# Fan_testing_rig_github.net
KiCad netlist of a schematic drawn in EasyEDA
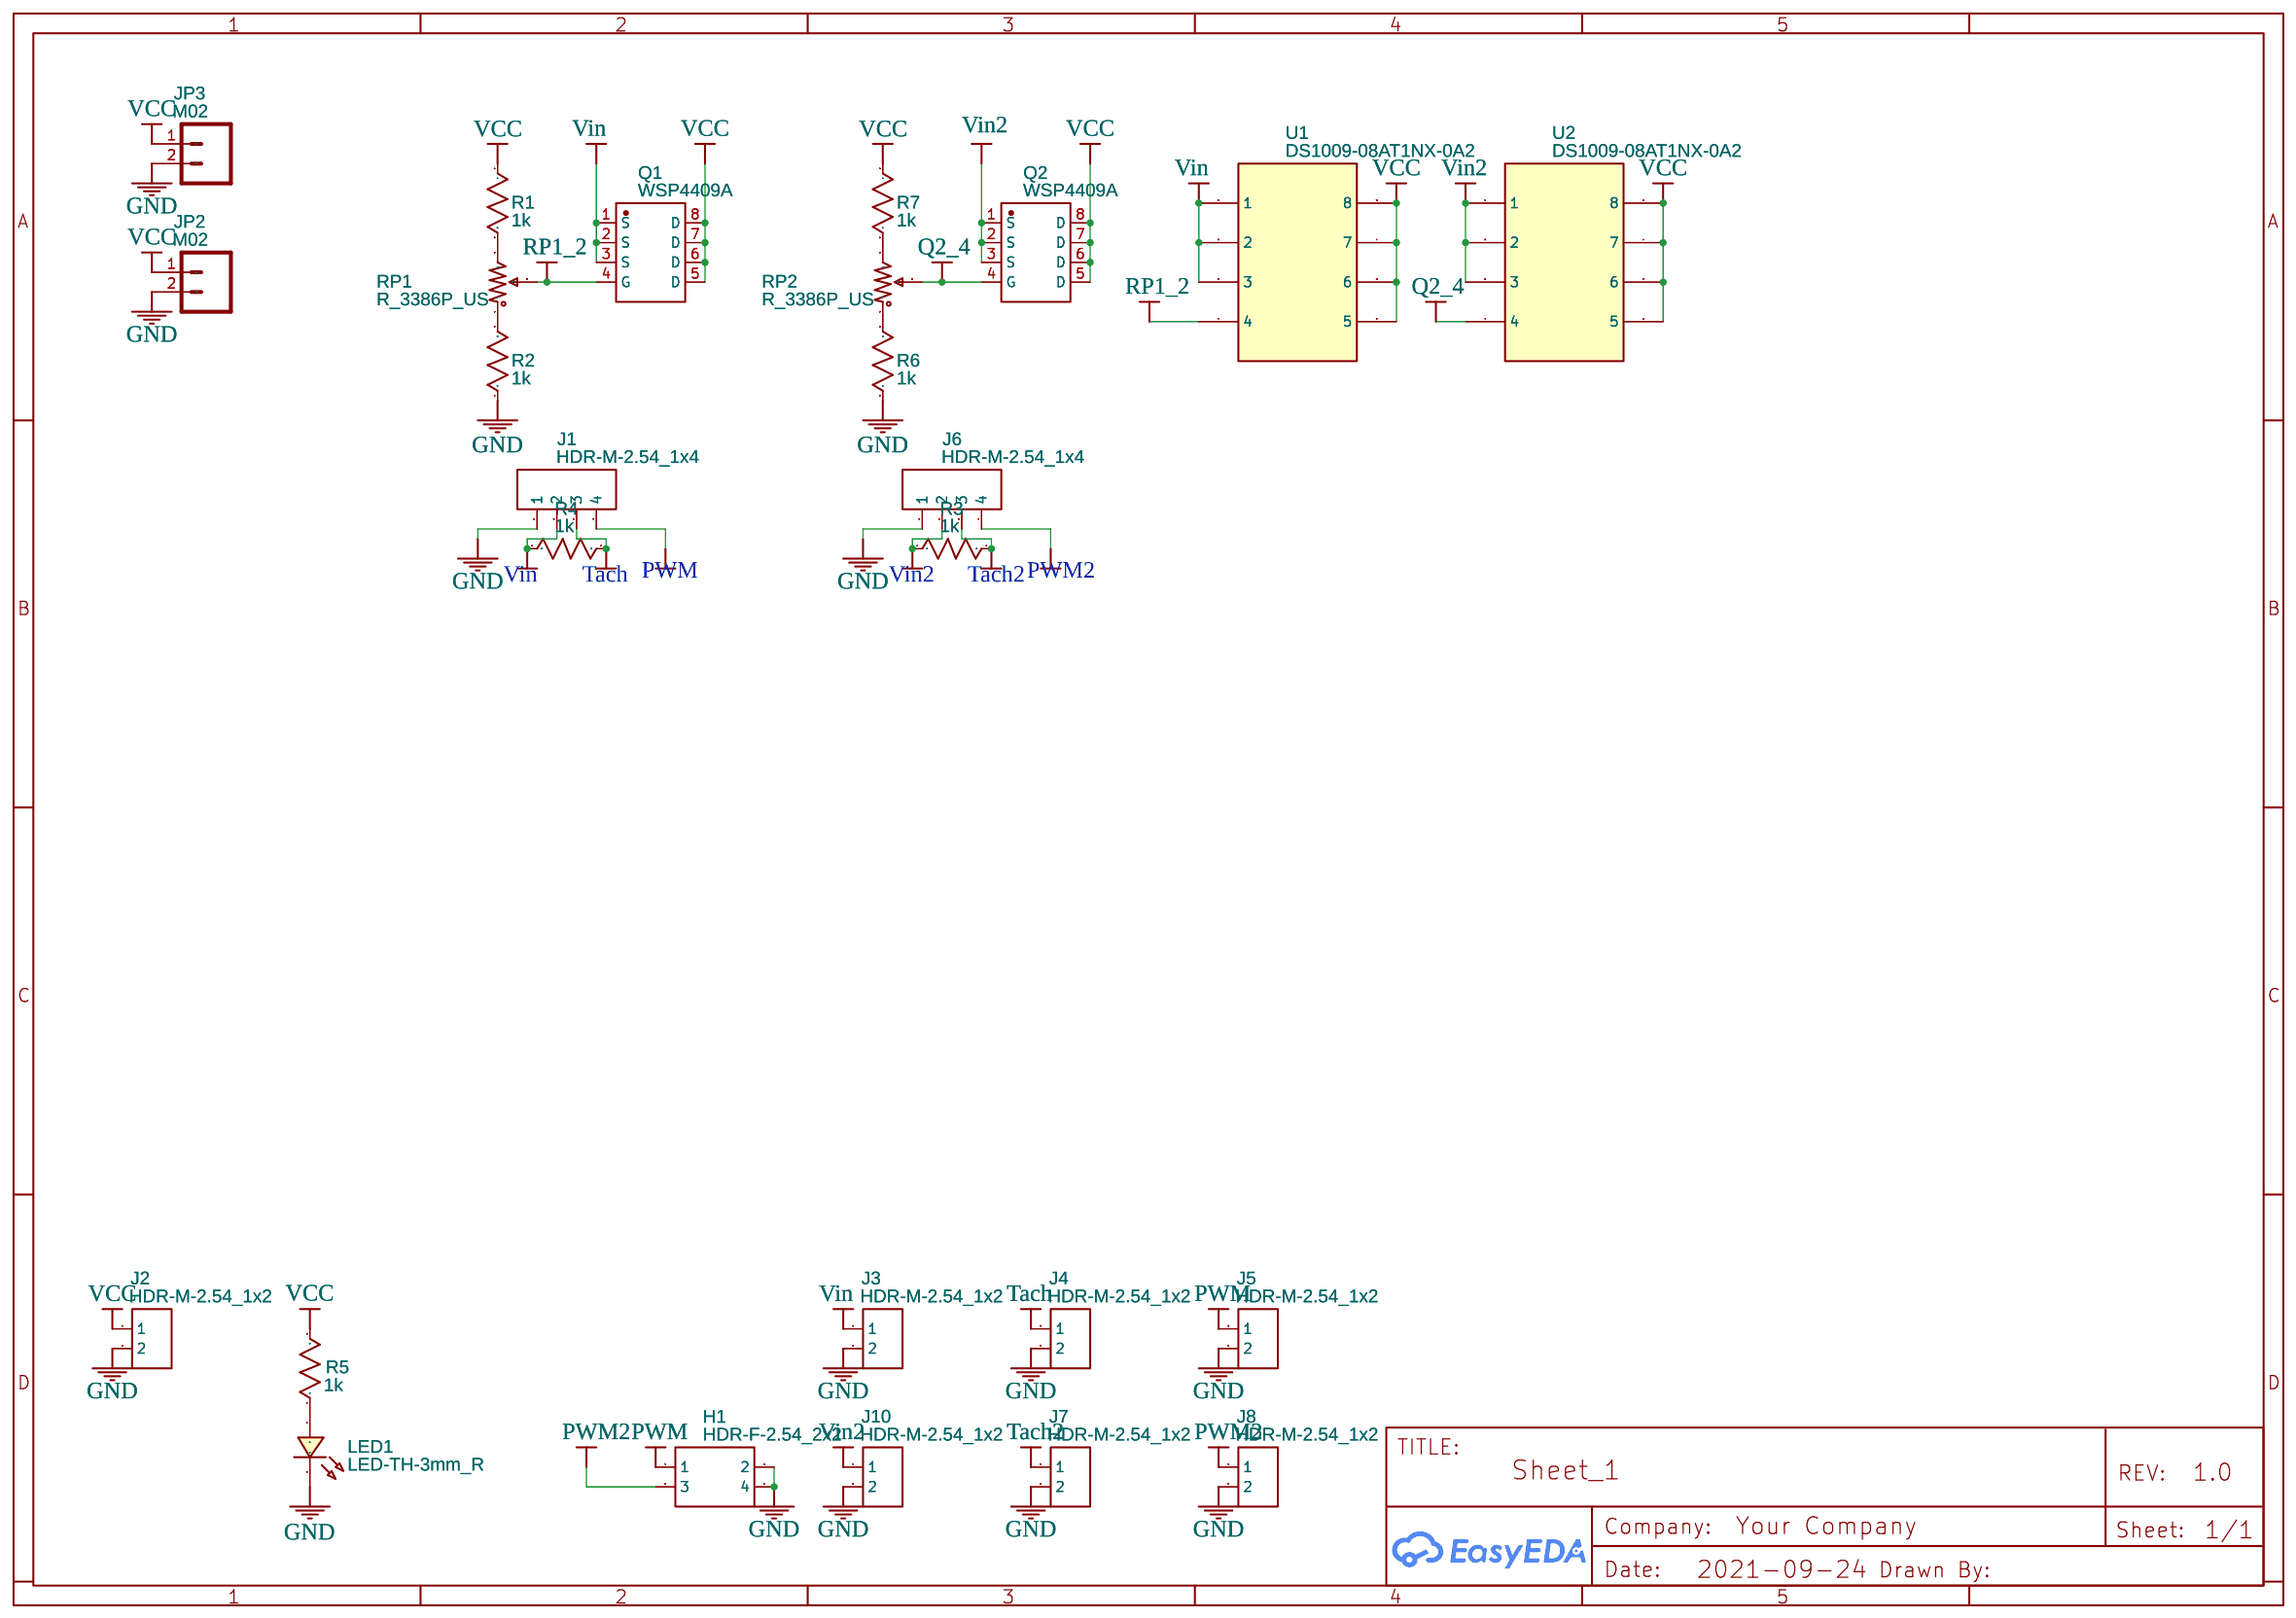
[diagram p0: main unit]
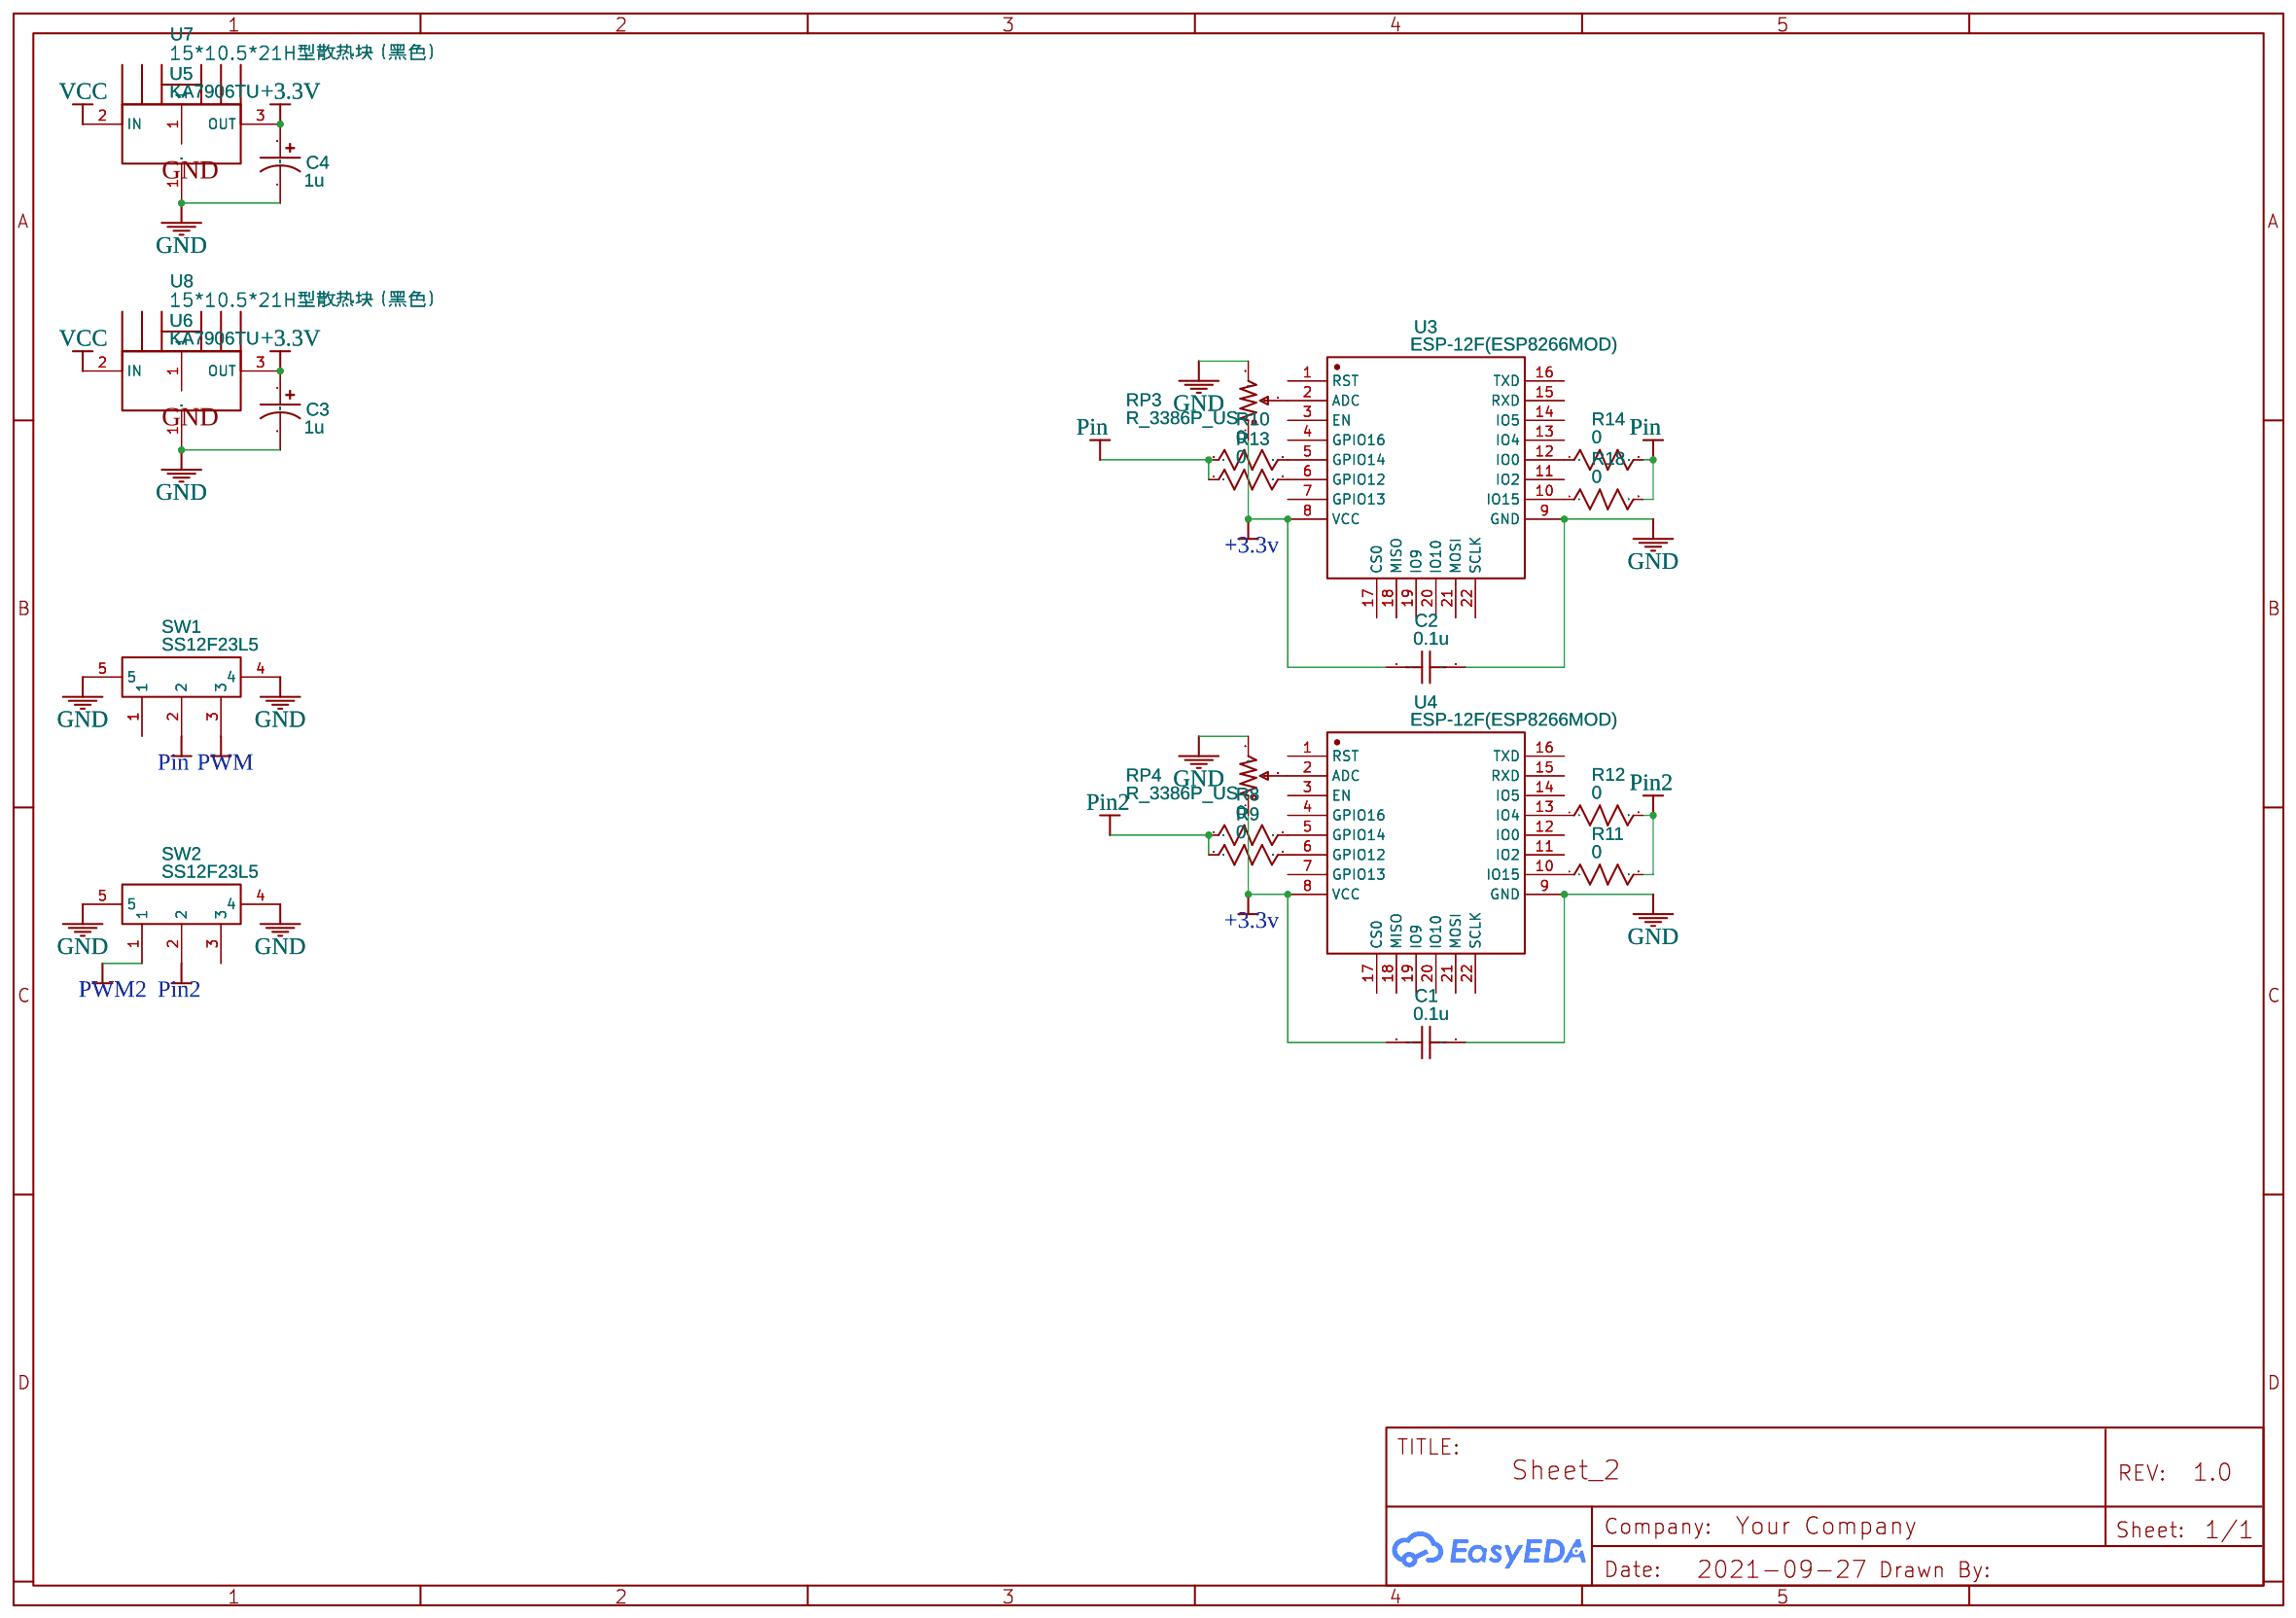
[diagram p1: PWM controll]

(export (version "E")
  (design (tool "Eeschema 10.0.6"))
  (components
    (comp (ref "H1")
      (value "HDR-F-2.54_2x2")
      (fields (field (name "BOM_Supplier Part") "C239342"))
      (libsource (lib "") (part "HDR-F-2.54_2x2"))
    )
    (comp (ref "J1")
      (value "HDR-M-2.54_1x4")
      (fields (field (name "BOM_Supplier Part") "C124378"))
      (libsource (lib "") (part "HDR-M-2.54_1x4"))
    )
    (comp (ref "J2")
      (value "HDR-M-2.54_1x2")
      (fields (field (name "BOM_Supplier Part") "C124375"))
      (libsource (lib "") (part "HDR-M-2.54_1x2"))
    )
    (comp (ref "J3")
      (value "HDR-M-2.54_1x2")
      (fields (field (name "BOM_Supplier Part") "C124375"))
      (libsource (lib "") (part "HDR-M-2.54_1x2"))
    )
    (comp (ref "J4")
      (value "HDR-M-2.54_1x2")
      (fields (field (name "BOM_Supplier Part") "C124375"))
      (libsource (lib "") (part "HDR-M-2.54_1x2"))
    )
    (comp (ref "J5")
      (value "HDR-M-2.54_1x2")
      (fields (field (name "BOM_Supplier Part") "C124375"))
      (libsource (lib "") (part "HDR-M-2.54_1x2"))
    )
    (comp (ref "J6")
      (value "HDR-M-2.54_1x4")
      (fields (field (name "BOM_Supplier Part") "C124378"))
      (libsource (lib "") (part "HDR-M-2.54_1x4"))
    )
    (comp (ref "J7")
      (value "HDR-M-2.54_1x2")
      (fields (field (name "BOM_Supplier Part") "C124375"))
      (libsource (lib "") (part "HDR-M-2.54_1x2"))
    )
    (comp (ref "J8")
      (value "HDR-M-2.54_1x2")
      (fields (field (name "BOM_Supplier Part") "C124375"))
      (libsource (lib "") (part "HDR-M-2.54_1x2"))
    )
    (comp (ref "J10")
      (value "HDR-M-2.54_1x2")
      (fields (field (name "BOM_Supplier Part") "C124375"))
      (libsource (lib "") (part "HDR-M-2.54_1x2"))
    )
    (comp (ref "JP2") (value "M02") (libsource (lib "") (part "M02")))
    (comp (ref "JP3") (value "M02") (libsource (lib "") (part "M02")))
    (comp (ref "LED1")
      (value "LED-TH-3mm_R")
      (fields
        (field (name "BOM_Manufacturer Part") "204-10SDRD/S530-A3-L")
        (field (name "BOM_Supplier Part") "C84774")
      )
      (libsource (lib "") (part "LED-TH-3mm_R"))
    )
    (comp (ref "Q1")
      (value "WSP4409A")
      (fields (field (name "BOM_Supplier Part") "C2880527"))
      (libsource (lib "") (part "WSP4409A"))
    )
    (comp (ref "Q2")
      (value "WSP4409A")
      (fields (field (name "BOM_Supplier Part") "C2880527"))
      (libsource (lib "") (part "WSP4409A"))
    )
    (comp (ref "R1") (value "1k") (libsource (lib "") (part "R_AXIAL-0.3_US_2")))
    (comp (ref "R2") (value "1k") (libsource (lib "") (part "R_AXIAL-0.3_US")))
    (comp (ref "R3") (value "1k") (libsource (lib "") (part "R_AXIAL-0.3_US_1")))
    (comp (ref "R4") (value "1k") (libsource (lib "") (part "R_AXIAL-0.3_US_1")))
    (comp (ref "R5") (value "1k") (libsource (lib "") (part "R_AXIAL-0.3_US")))
    (comp (ref "R6") (value "1k") (libsource (lib "") (part "R_AXIAL-0.3_US")))
    (comp (ref "R7") (value "1k") (libsource (lib "") (part "R_AXIAL-0.3_US_2")))
    (comp (ref "RP1") (value "R_3386P_US") (libsource (lib "") (part "R_3386P_US")))
    (comp (ref "RP2") (value "R_3386P_US") (libsource (lib "") (part "R_3386P_US")))
    (comp (ref "U1")
      (value "DS1009-08AT1NX-0A2")
      (fields (field (name "BOM_Supplier Part") "C72124"))
      (libsource (lib "") (part "DS1009-08AT1NX-0A2"))
    )
    (comp (ref "U2")
      (value "DS1009-08AT1NX-0A2")
      (fields (field (name "BOM_Supplier Part") "C72124"))
      (libsource (lib "") (part "DS1009-08AT1NX-0A2"))
    )
    (comp (ref "C1") (value "0.1u") (libsource (lib "") (part "C_0805_US")))
    (comp (ref "C2") (value "0.1u") (libsource (lib "") (part "C_0805_US")))
    (comp (ref "C3") (value "1u") (libsource (lib "") (part "CE_TH_D8.0×F3.5_US")))
    (comp (ref "C4") (value "1u") (libsource (lib "") (part "CE_TH_D8.0×F3.5_US")))
    (comp (ref "R8") (value "0") (libsource (lib "") (part "R_AXIAL-0.3_US")))
    (comp (ref "R9") (value "0") (libsource (lib "") (part "R_AXIAL-0.3_US")))
    (comp (ref "R10") (value "0") (libsource (lib "") (part "R_AXIAL-0.3_US")))
    (comp (ref "R11") (value "0") (libsource (lib "") (part "R_AXIAL-0.3_US")))
    (comp (ref "R12") (value "0") (libsource (lib "") (part "R_AXIAL-0.3_US")))
    (comp (ref "R13") (value "0") (libsource (lib "") (part "R_AXIAL-0.3_US")))
    (comp (ref "R14") (value "0") (libsource (lib "") (part "R_AXIAL-0.3_US")))
    (comp (ref "R18") (value "0") (libsource (lib "") (part "R_AXIAL-0.3_US")))
    (comp (ref "RP3") (value "R_3386P_US") (libsource (lib "") (part "R_3386P_US")))
    (comp (ref "RP4") (value "R_3386P_US") (libsource (lib "") (part "R_3386P_US")))
    (comp (ref "SW1")
      (value "SS12F23L5")
      (fields (field (name "BOM_Supplier Part") "C2884749"))
      (libsource (lib "") (part "SS12F23L5"))
    )
    (comp (ref "SW2")
      (value "SS12F23L5")
      (fields (field (name "BOM_Supplier Part") "C2884749"))
      (libsource (lib "") (part "SS12F23L5"))
    )
    (comp (ref "U3")
      (value "ESP-12F(ESP8266MOD)")
      (fields (field (name "BOM_Supplier Part") "C82891"))
      (libsource (lib "") (part "ESP-12F(ESP8266MOD)"))
    )
    (comp (ref "U4")
      (value "ESP-12F(ESP8266MOD)")
      (fields (field (name "BOM_Supplier Part") "C82891"))
      (libsource (lib "") (part "ESP-12F(ESP8266MOD)"))
    )
    (comp (ref "U5")
      (value "KA7906TU")
      (fields (field (name "BOM_Supplier Part") "C112610"))
      (libsource (lib "") (part "KA7906TU"))
    )
    (comp (ref "U6")
      (value "KA7906TU")
      (fields (field (name "BOM_Supplier Part") "C112610"))
      (libsource (lib "") (part "KA7906TU"))
    )
    (comp (ref "U7")
      (value "15*10.5*21H型散热块（黑色）")
      (fields (field (name "BOM_Supplier Part") "C116600"))
      (libsource (lib "") (part "15*10.5*21H型散热块（黑色）"))
    )
    (comp (ref "U8")
      (value "15*10.5*21H型散热块（黑色）")
      (fields (field (name "BOM_Supplier Part") "C116600"))
      (libsource (lib "") (part "15*10.5*21H型散热块（黑色）"))
    )
  )
  (nets
    (net (code "1") (name "+3.3V") (class "Default")
      (node (ref "C3") (pin "1") (pinfunction "1_1") (pintype "unspecified"))
      (node (ref "C4") (pin "1") (pinfunction "1_1") (pintype "unspecified"))
      (node (ref "U5") (pin "3") (pinfunction "OUT_3") (pintype "passive"))
      (node (ref "U6") (pin "3") (pinfunction "OUT_3") (pintype "passive"))
    )
    (net (code "2") (name "+3.3v") (class "Default")
      (node (ref "C1") (pin "1") (pinfunction "1_1") (pintype "unspecified"))
      (node (ref "C2") (pin "1") (pinfunction "1_1") (pintype "unspecified"))
      (node (ref "RP3") (pin "1") (pinfunction "1_1") (pintype "unspecified"))
      (node (ref "RP4") (pin "1") (pinfunction "1_1") (pintype "unspecified"))
      (node (ref "U3") (pin "8") (pinfunction "VCC_8") (pintype "unspecified"))
      (node (ref "U4") (pin "8") (pinfunction "VCC_8") (pintype "unspecified"))
    )
    (net (code "3") (name "GND") (class "Default")
      (node (ref "C1") (pin "2") (pinfunction "2_2") (pintype "unspecified"))
      (node (ref "C2") (pin "2") (pinfunction "2_2") (pintype "unspecified"))
      (node (ref "C3") (pin "2") (pinfunction "2_2") (pintype "unspecified"))
      (node (ref "C4") (pin "2") (pinfunction "2_2") (pintype "unspecified"))
      (node (ref "H1") (pin "2") (pinfunction "2_2") (pintype "unspecified"))
      (node (ref "H1") (pin "4") (pinfunction "4_4") (pintype "unspecified"))
      (node (ref "J1") (pin "1") (pinfunction "1_1") (pintype "unspecified"))
      (node (ref "J10") (pin "2") (pinfunction "2_2") (pintype "unspecified"))
      (node (ref "J2") (pin "2") (pinfunction "2_2") (pintype "unspecified"))
      (node (ref "J3") (pin "2") (pinfunction "2_2") (pintype "unspecified"))
      (node (ref "J4") (pin "2") (pinfunction "2_2") (pintype "unspecified"))
      (node (ref "J5") (pin "2") (pinfunction "2_2") (pintype "unspecified"))
      (node (ref "J6") (pin "1") (pinfunction "1_1") (pintype "unspecified"))
      (node (ref "J7") (pin "2") (pinfunction "2_2") (pintype "unspecified"))
      (node (ref "J8") (pin "2") (pinfunction "2_2") (pintype "unspecified"))
      (node (ref "JP2") (pin "2") (pinfunction "2_2") (pintype "unspecified"))
      (node (ref "JP3") (pin "2") (pinfunction "2_2") (pintype "unspecified"))
      (node (ref "LED1") (pin "2") (pinfunction "2_2") (pintype "unspecified"))
      (node (ref "R2") (pin "1") (pinfunction "1_1") (pintype "unspecified"))
      (node (ref "R6") (pin "1") (pinfunction "1_1") (pintype "unspecified"))
      (node (ref "RP3") (pin "3") (pinfunction "3_3") (pintype "unspecified"))
      (node (ref "RP4") (pin "3") (pinfunction "3_3") (pintype "unspecified"))
      (node (ref "SW1") (pin "4") (pinfunction "4_4") (pintype "unspecified"))
      (node (ref "SW1") (pin "5") (pinfunction "5_5") (pintype "unspecified"))
      (node (ref "SW2") (pin "4") (pinfunction "4_4") (pintype "unspecified"))
      (node (ref "SW2") (pin "5") (pinfunction "5_5") (pintype "unspecified"))
      (node (ref "U3") (pin "9") (pinfunction "GND_9") (pintype "unspecified"))
      (node (ref "U4") (pin "9") (pinfunction "GND_9") (pintype "unspecified"))
      (node (ref "U5") (pin "1") (pinfunction "GND_1") (pintype "passive"))
      (node (ref "U6") (pin "1") (pinfunction "GND_1") (pintype "passive"))
    )
    (net (code "4") (name "Net-(LED1-Pad1)") (class "Default")
      (node (ref "LED1") (pin "1") (pinfunction "1_1") (pintype "unspecified"))
      (node (ref "R5") (pin "1") (pinfunction "1_1") (pintype "unspecified"))
    )
    (net (code "5") (name "Net-(R1-Pad2)") (class "Default")
      (node (ref "R1") (pin "2") (pinfunction "2_2") (pintype "unspecified"))
      (node (ref "RP1") (pin "3") (pinfunction "3_3") (pintype "unspecified"))
    )
    (net (code "6") (name "Net-(R2-Pad2)") (class "Default")
      (node (ref "R2") (pin "2") (pinfunction "2_2") (pintype "unspecified"))
      (node (ref "RP1") (pin "1") (pinfunction "1_1") (pintype "unspecified"))
    )
    (net (code "7") (name "Net-(R6-Pad2)") (class "Default")
      (node (ref "R6") (pin "2") (pinfunction "2_2") (pintype "unspecified"))
      (node (ref "RP2") (pin "1") (pinfunction "1_1") (pintype "unspecified"))
    )
    (net (code "8") (name "Net-(R7-Pad2)") (class "Default")
      (node (ref "R7") (pin "2") (pinfunction "2_2") (pintype "unspecified"))
      (node (ref "RP2") (pin "3") (pinfunction "3_3") (pintype "unspecified"))
    )
    (net (code "9") (name "Net-(U3-ADC)") (class "Default")
      (node (ref "RP3") (pin "2") (pinfunction "2_2") (pintype "unspecified"))
      (node (ref "U3") (pin "2") (pinfunction "ADC_2") (pintype "unspecified"))
    )
    (net (code "10") (name "Net-(U3-GPIO12)") (class "Default")
      (node (ref "R13") (pin "2") (pinfunction "2_2") (pintype "unspecified"))
      (node (ref "U3") (pin "6") (pinfunction "GPIO12_6") (pintype "unspecified"))
    )
    (net (code "11") (name "Net-(U3-GPIO14)") (class "Default")
      (node (ref "R10") (pin "2") (pinfunction "2_2") (pintype "unspecified"))
      (node (ref "U3") (pin "5") (pinfunction "GPIO14_5") (pintype "unspecified"))
    )
    (net (code "12") (name "Net-(U3-IO0)") (class "Default")
      (node (ref "R14") (pin "1") (pinfunction "1_1") (pintype "unspecified"))
      (node (ref "U3") (pin "12") (pinfunction "IO0_12") (pintype "unspecified"))
    )
    (net (code "13") (name "Net-(U3-IO15)") (class "Default")
      (node (ref "R18") (pin "1") (pinfunction "1_1") (pintype "unspecified"))
      (node (ref "U3") (pin "10") (pinfunction "IO15_10") (pintype "unspecified"))
    )
    (net (code "14") (name "Net-(U4-ADC)") (class "Default")
      (node (ref "RP4") (pin "2") (pinfunction "2_2") (pintype "unspecified"))
      (node (ref "U4") (pin "2") (pinfunction "ADC_2") (pintype "unspecified"))
    )
    (net (code "15") (name "Net-(U4-GPIO12)") (class "Default")
      (node (ref "R9") (pin "2") (pinfunction "2_2") (pintype "unspecified"))
      (node (ref "U4") (pin "6") (pinfunction "GPIO12_6") (pintype "unspecified"))
    )
    (net (code "16") (name "Net-(U4-GPIO14)") (class "Default")
      (node (ref "R8") (pin "2") (pinfunction "2_2") (pintype "unspecified"))
      (node (ref "U4") (pin "5") (pinfunction "GPIO14_5") (pintype "unspecified"))
    )
    (net (code "17") (name "Net-(U4-IO4)") (class "Default")
      (node (ref "R12") (pin "1") (pinfunction "1_1") (pintype "unspecified"))
      (node (ref "U4") (pin "13") (pinfunction "IO4_13") (pintype "unspecified"))
    )
    (net (code "18") (name "Net-(U4-IO15)") (class "Default")
      (node (ref "R11") (pin "1") (pinfunction "1_1") (pintype "unspecified"))
      (node (ref "U4") (pin "10") (pinfunction "IO15_10") (pintype "unspecified"))
    )
    (net (code "19") (name "PWM") (class "Default")
      (node (ref "H1") (pin "1") (pinfunction "1_1") (pintype "unspecified"))
      (node (ref "J1") (pin "4") (pinfunction "4_4") (pintype "unspecified"))
      (node (ref "J5") (pin "1") (pinfunction "1_1") (pintype "unspecified"))
      (node (ref "SW1") (pin "3") (pinfunction "3_3") (pintype "unspecified"))
    )
    (net (code "20") (name "PWM2") (class "Default")
      (node (ref "H1") (pin "3") (pinfunction "3_3") (pintype "unspecified"))
      (node (ref "J6") (pin "4") (pinfunction "4_4") (pintype "unspecified"))
      (node (ref "J8") (pin "1") (pinfunction "1_1") (pintype "unspecified"))
      (node (ref "SW2") (pin "1") (pinfunction "1_1") (pintype "unspecified"))
    )
    (net (code "21") (name "Pin") (class "Default")
      (node (ref "R10") (pin "1") (pinfunction "1_1") (pintype "unspecified"))
      (node (ref "R13") (pin "1") (pinfunction "1_1") (pintype "unspecified"))
      (node (ref "R14") (pin "2") (pinfunction "2_2") (pintype "unspecified"))
      (node (ref "R18") (pin "2") (pinfunction "2_2") (pintype "unspecified"))
      (node (ref "SW1") (pin "2") (pinfunction "2_2") (pintype "unspecified"))
    )
    (net (code "22") (name "Pin2") (class "Default")
      (node (ref "R11") (pin "2") (pinfunction "2_2") (pintype "unspecified"))
      (node (ref "R12") (pin "2") (pinfunction "2_2") (pintype "unspecified"))
      (node (ref "R8") (pin "1") (pinfunction "1_1") (pintype "unspecified"))
      (node (ref "R9") (pin "1") (pinfunction "1_1") (pintype "unspecified"))
      (node (ref "SW2") (pin "2") (pinfunction "2_2") (pintype "unspecified"))
    )
    (net (code "23") (name "Q2_4") (class "Default")
      (node (ref "Q2") (pin "4") (pinfunction "G_4") (pintype "unspecified"))
      (node (ref "RP2") (pin "2") (pinfunction "2_2") (pintype "unspecified"))
      (node (ref "U2") (pin "4") (pinfunction "4_4") (pintype "input"))
    )
    (net (code "24") (name "RP1_2") (class "Default")
      (node (ref "Q1") (pin "4") (pinfunction "G_4") (pintype "unspecified"))
      (node (ref "RP1") (pin "2") (pinfunction "2_2") (pintype "unspecified"))
      (node (ref "U1") (pin "4") (pinfunction "4_4") (pintype "input"))
    )
    (net (code "25") (name "Tach") (class "Default")
      (node (ref "J1") (pin "3") (pinfunction "3_3") (pintype "unspecified"))
      (node (ref "J4") (pin "1") (pinfunction "1_1") (pintype "unspecified"))
      (node (ref "R4") (pin "2") (pinfunction "2_2") (pintype "unspecified"))
    )
    (net (code "26") (name "Tach2") (class "Default")
      (node (ref "J6") (pin "3") (pinfunction "3_3") (pintype "unspecified"))
      (node (ref "J7") (pin "1") (pinfunction "1_1") (pintype "unspecified"))
      (node (ref "R3") (pin "2") (pinfunction "2_2") (pintype "unspecified"))
    )
    (net (code "27") (name "VCC") (class "Default")
      (node (ref "J2") (pin "1") (pinfunction "1_1") (pintype "unspecified"))
      (node (ref "JP2") (pin "1") (pinfunction "1_1") (pintype "unspecified"))
      (node (ref "JP3") (pin "1") (pinfunction "1_1") (pintype "unspecified"))
      (node (ref "Q1") (pin "5") (pinfunction "D_5") (pintype "unspecified"))
      (node (ref "Q1") (pin "6") (pinfunction "D_6") (pintype "unspecified"))
      (node (ref "Q1") (pin "7") (pinfunction "D_7") (pintype "unspecified"))
      (node (ref "Q1") (pin "8") (pinfunction "D_8") (pintype "unspecified"))
      (node (ref "Q2") (pin "5") (pinfunction "D_5") (pintype "unspecified"))
      (node (ref "Q2") (pin "6") (pinfunction "D_6") (pintype "unspecified"))
      (node (ref "Q2") (pin "7") (pinfunction "D_7") (pintype "unspecified"))
      (node (ref "Q2") (pin "8") (pinfunction "D_8") (pintype "unspecified"))
      (node (ref "R1") (pin "1") (pinfunction "1_1") (pintype "unspecified"))
      (node (ref "R5") (pin "2") (pinfunction "2_2") (pintype "unspecified"))
      (node (ref "R7") (pin "1") (pinfunction "1_1") (pintype "unspecified"))
      (node (ref "U1") (pin "5") (pinfunction "5_5") (pintype "input"))
      (node (ref "U1") (pin "6") (pinfunction "6_6") (pintype "input"))
      (node (ref "U1") (pin "7") (pinfunction "7_7") (pintype "input"))
      (node (ref "U1") (pin "8") (pinfunction "8_8") (pintype "input"))
      (node (ref "U2") (pin "5") (pinfunction "5_5") (pintype "input"))
      (node (ref "U2") (pin "6") (pinfunction "6_6") (pintype "input"))
      (node (ref "U2") (pin "7") (pinfunction "7_7") (pintype "input"))
      (node (ref "U2") (pin "8") (pinfunction "8_8") (pintype "input"))
      (node (ref "U5") (pin "2") (pinfunction "IN_2") (pintype "passive"))
      (node (ref "U6") (pin "2") (pinfunction "IN_2") (pintype "passive"))
    )
    (net (code "28") (name "Vin") (class "Default")
      (node (ref "J1") (pin "2") (pinfunction "2_2") (pintype "unspecified"))
      (node (ref "J3") (pin "1") (pinfunction "1_1") (pintype "unspecified"))
      (node (ref "Q1") (pin "1") (pinfunction "S_1") (pintype "unspecified"))
      (node (ref "Q1") (pin "2") (pinfunction "S_2") (pintype "unspecified"))
      (node (ref "Q1") (pin "3") (pinfunction "S_3") (pintype "unspecified"))
      (node (ref "R4") (pin "1") (pinfunction "1_1") (pintype "unspecified"))
      (node (ref "U1") (pin "1") (pinfunction "1_1") (pintype "input"))
      (node (ref "U1") (pin "2") (pinfunction "2_2") (pintype "input"))
      (node (ref "U1") (pin "3") (pinfunction "3_3") (pintype "input"))
    )
    (net (code "29") (name "Vin2") (class "Default")
      (node (ref "J10") (pin "1") (pinfunction "1_1") (pintype "unspecified"))
      (node (ref "J6") (pin "2") (pinfunction "2_2") (pintype "unspecified"))
      (node (ref "Q2") (pin "1") (pinfunction "S_1") (pintype "unspecified"))
      (node (ref "Q2") (pin "2") (pinfunction "S_2") (pintype "unspecified"))
      (node (ref "Q2") (pin "3") (pinfunction "S_3") (pintype "unspecified"))
      (node (ref "R3") (pin "1") (pinfunction "1_1") (pintype "unspecified"))
      (node (ref "U2") (pin "1") (pinfunction "1_1") (pintype "input"))
      (node (ref "U2") (pin "2") (pinfunction "2_2") (pintype "input"))
      (node (ref "U2") (pin "3") (pinfunction "3_3") (pintype "input"))
    )
    (net (code "30") (name "unconnected-(SW1-Pad1)") (class "Default")
      (node (ref "SW1") (pin "1") (pinfunction "1_1") (pintype "unspecified"))
    )
    (net (code "31") (name "unconnected-(SW2-Pad3)") (class "Default")
      (node (ref "SW2") (pin "3") (pinfunction "3_3") (pintype "unspecified"))
    )
    (net (code "32") (name "unconnected-(U3-CS0-Pad17)") (class "Default")
      (node (ref "U3") (pin "17") (pinfunction "CS0_17") (pintype "unspecified"))
    )
    (net (code "33") (name "unconnected-(U3-EN-Pad3)") (class "Default")
      (node (ref "U3") (pin "3") (pinfunction "EN_3") (pintype "unspecified"))
    )
    (net (code "34") (name "unconnected-(U3-GPIO13-Pad7)") (class "Default")
      (node (ref "U3") (pin "7") (pinfunction "GPIO13_7") (pintype "unspecified"))
    )
    (net (code "35") (name "unconnected-(U3-GPIO16-Pad4)") (class "Default")
      (node (ref "U3") (pin "4") (pinfunction "GPIO16_4") (pintype "unspecified"))
    )
    (net (code "36") (name "unconnected-(U3-IO2-Pad11)") (class "Default")
      (node (ref "U3") (pin "11") (pinfunction "IO2_11") (pintype "unspecified"))
    )
    (net (code "37") (name "unconnected-(U3-IO4-Pad13)") (class "Default")
      (node (ref "U3") (pin "13") (pinfunction "IO4_13") (pintype "unspecified"))
    )
    (net (code "38") (name "unconnected-(U3-IO5-Pad14)") (class "Default")
      (node (ref "U3") (pin "14") (pinfunction "IO5_14") (pintype "unspecified"))
    )
    (net (code "39") (name "unconnected-(U3-IO9-Pad19)") (class "Default")
      (node (ref "U3") (pin "19") (pinfunction "IO9_19") (pintype "unspecified"))
    )
    (net (code "40") (name "unconnected-(U3-IO10-Pad20)") (class "Default")
      (node (ref "U3") (pin "20") (pinfunction "IO10_20") (pintype "unspecified"))
    )
    (net (code "41") (name "unconnected-(U3-MISO-Pad18)") (class "Default")
      (node (ref "U3") (pin "18") (pinfunction "MISO_18") (pintype "unspecified"))
    )
    (net (code "42") (name "unconnected-(U3-MOSI-Pad21)") (class "Default")
      (node (ref "U3") (pin "21") (pinfunction "MOSI_21") (pintype "unspecified"))
    )
    (net (code "43") (name "unconnected-(U3-RST-Pad1)") (class "Default")
      (node (ref "U3") (pin "1") (pinfunction "RST_1") (pintype "unspecified"))
    )
    (net (code "44") (name "unconnected-(U3-RXD-Pad15)") (class "Default")
      (node (ref "U3") (pin "15") (pinfunction "RXD_15") (pintype "unspecified"))
    )
    (net (code "45") (name "unconnected-(U3-SCLK-Pad22)") (class "Default")
      (node (ref "U3") (pin "22") (pinfunction "SCLK_22") (pintype "unspecified"))
    )
    (net (code "46") (name "unconnected-(U3-TXD-Pad16)") (class "Default")
      (node (ref "U3") (pin "16") (pinfunction "TXD_16") (pintype "unspecified"))
    )
    (net (code "47") (name "unconnected-(U4-CS0-Pad17)") (class "Default")
      (node (ref "U4") (pin "17") (pinfunction "CS0_17") (pintype "unspecified"))
    )
    (net (code "48") (name "unconnected-(U4-EN-Pad3)") (class "Default")
      (node (ref "U4") (pin "3") (pinfunction "EN_3") (pintype "unspecified"))
    )
    (net (code "49") (name "unconnected-(U4-GPIO13-Pad7)") (class "Default")
      (node (ref "U4") (pin "7") (pinfunction "GPIO13_7") (pintype "unspecified"))
    )
    (net (code "50") (name "unconnected-(U4-GPIO16-Pad4)") (class "Default")
      (node (ref "U4") (pin "4") (pinfunction "GPIO16_4") (pintype "unspecified"))
    )
    (net (code "51") (name "unconnected-(U4-IO0-Pad12)") (class "Default")
      (node (ref "U4") (pin "12") (pinfunction "IO0_12") (pintype "unspecified"))
    )
    (net (code "52") (name "unconnected-(U4-IO2-Pad11)") (class "Default")
      (node (ref "U4") (pin "11") (pinfunction "IO2_11") (pintype "unspecified"))
    )
    (net (code "53") (name "unconnected-(U4-IO5-Pad14)") (class "Default")
      (node (ref "U4") (pin "14") (pinfunction "IO5_14") (pintype "unspecified"))
    )
    (net (code "54") (name "unconnected-(U4-IO9-Pad19)") (class "Default")
      (node (ref "U4") (pin "19") (pinfunction "IO9_19") (pintype "unspecified"))
    )
    (net (code "55") (name "unconnected-(U4-IO10-Pad20)") (class "Default")
      (node (ref "U4") (pin "20") (pinfunction "IO10_20") (pintype "unspecified"))
    )
    (net (code "56") (name "unconnected-(U4-MISO-Pad18)") (class "Default")
      (node (ref "U4") (pin "18") (pinfunction "MISO_18") (pintype "unspecified"))
    )
    (net (code "57") (name "unconnected-(U4-MOSI-Pad21)") (class "Default")
      (node (ref "U4") (pin "21") (pinfunction "MOSI_21") (pintype "unspecified"))
    )
    (net (code "58") (name "unconnected-(U4-RST-Pad1)") (class "Default")
      (node (ref "U4") (pin "1") (pinfunction "RST_1") (pintype "unspecified"))
    )
    (net (code "59") (name "unconnected-(U4-RXD-Pad15)") (class "Default")
      (node (ref "U4") (pin "15") (pinfunction "RXD_15") (pintype "unspecified"))
    )
    (net (code "60") (name "unconnected-(U4-SCLK-Pad22)") (class "Default")
      (node (ref "U4") (pin "22") (pinfunction "SCLK_22") (pintype "unspecified"))
    )
    (net (code "61") (name "unconnected-(U4-TXD-Pad16)") (class "Default")
      (node (ref "U4") (pin "16") (pinfunction "TXD_16") (pintype "unspecified"))
    )
    (net (code "62") (name "unconnected-(U7-Pad1)") (class "Default")
      (node (ref "U7") (pin "1") (pinfunction "1_1") (pintype "unspecified"))
    )
    (net (code "63") (name "unconnected-(U8-Pad1)") (class "Default")
      (node (ref "U8") (pin "1") (pinfunction "1_1") (pintype "unspecified"))
    )
  )
)
